# POWER_STAGE.net
KiCad netlist of a schematic drawn in Altium Designer
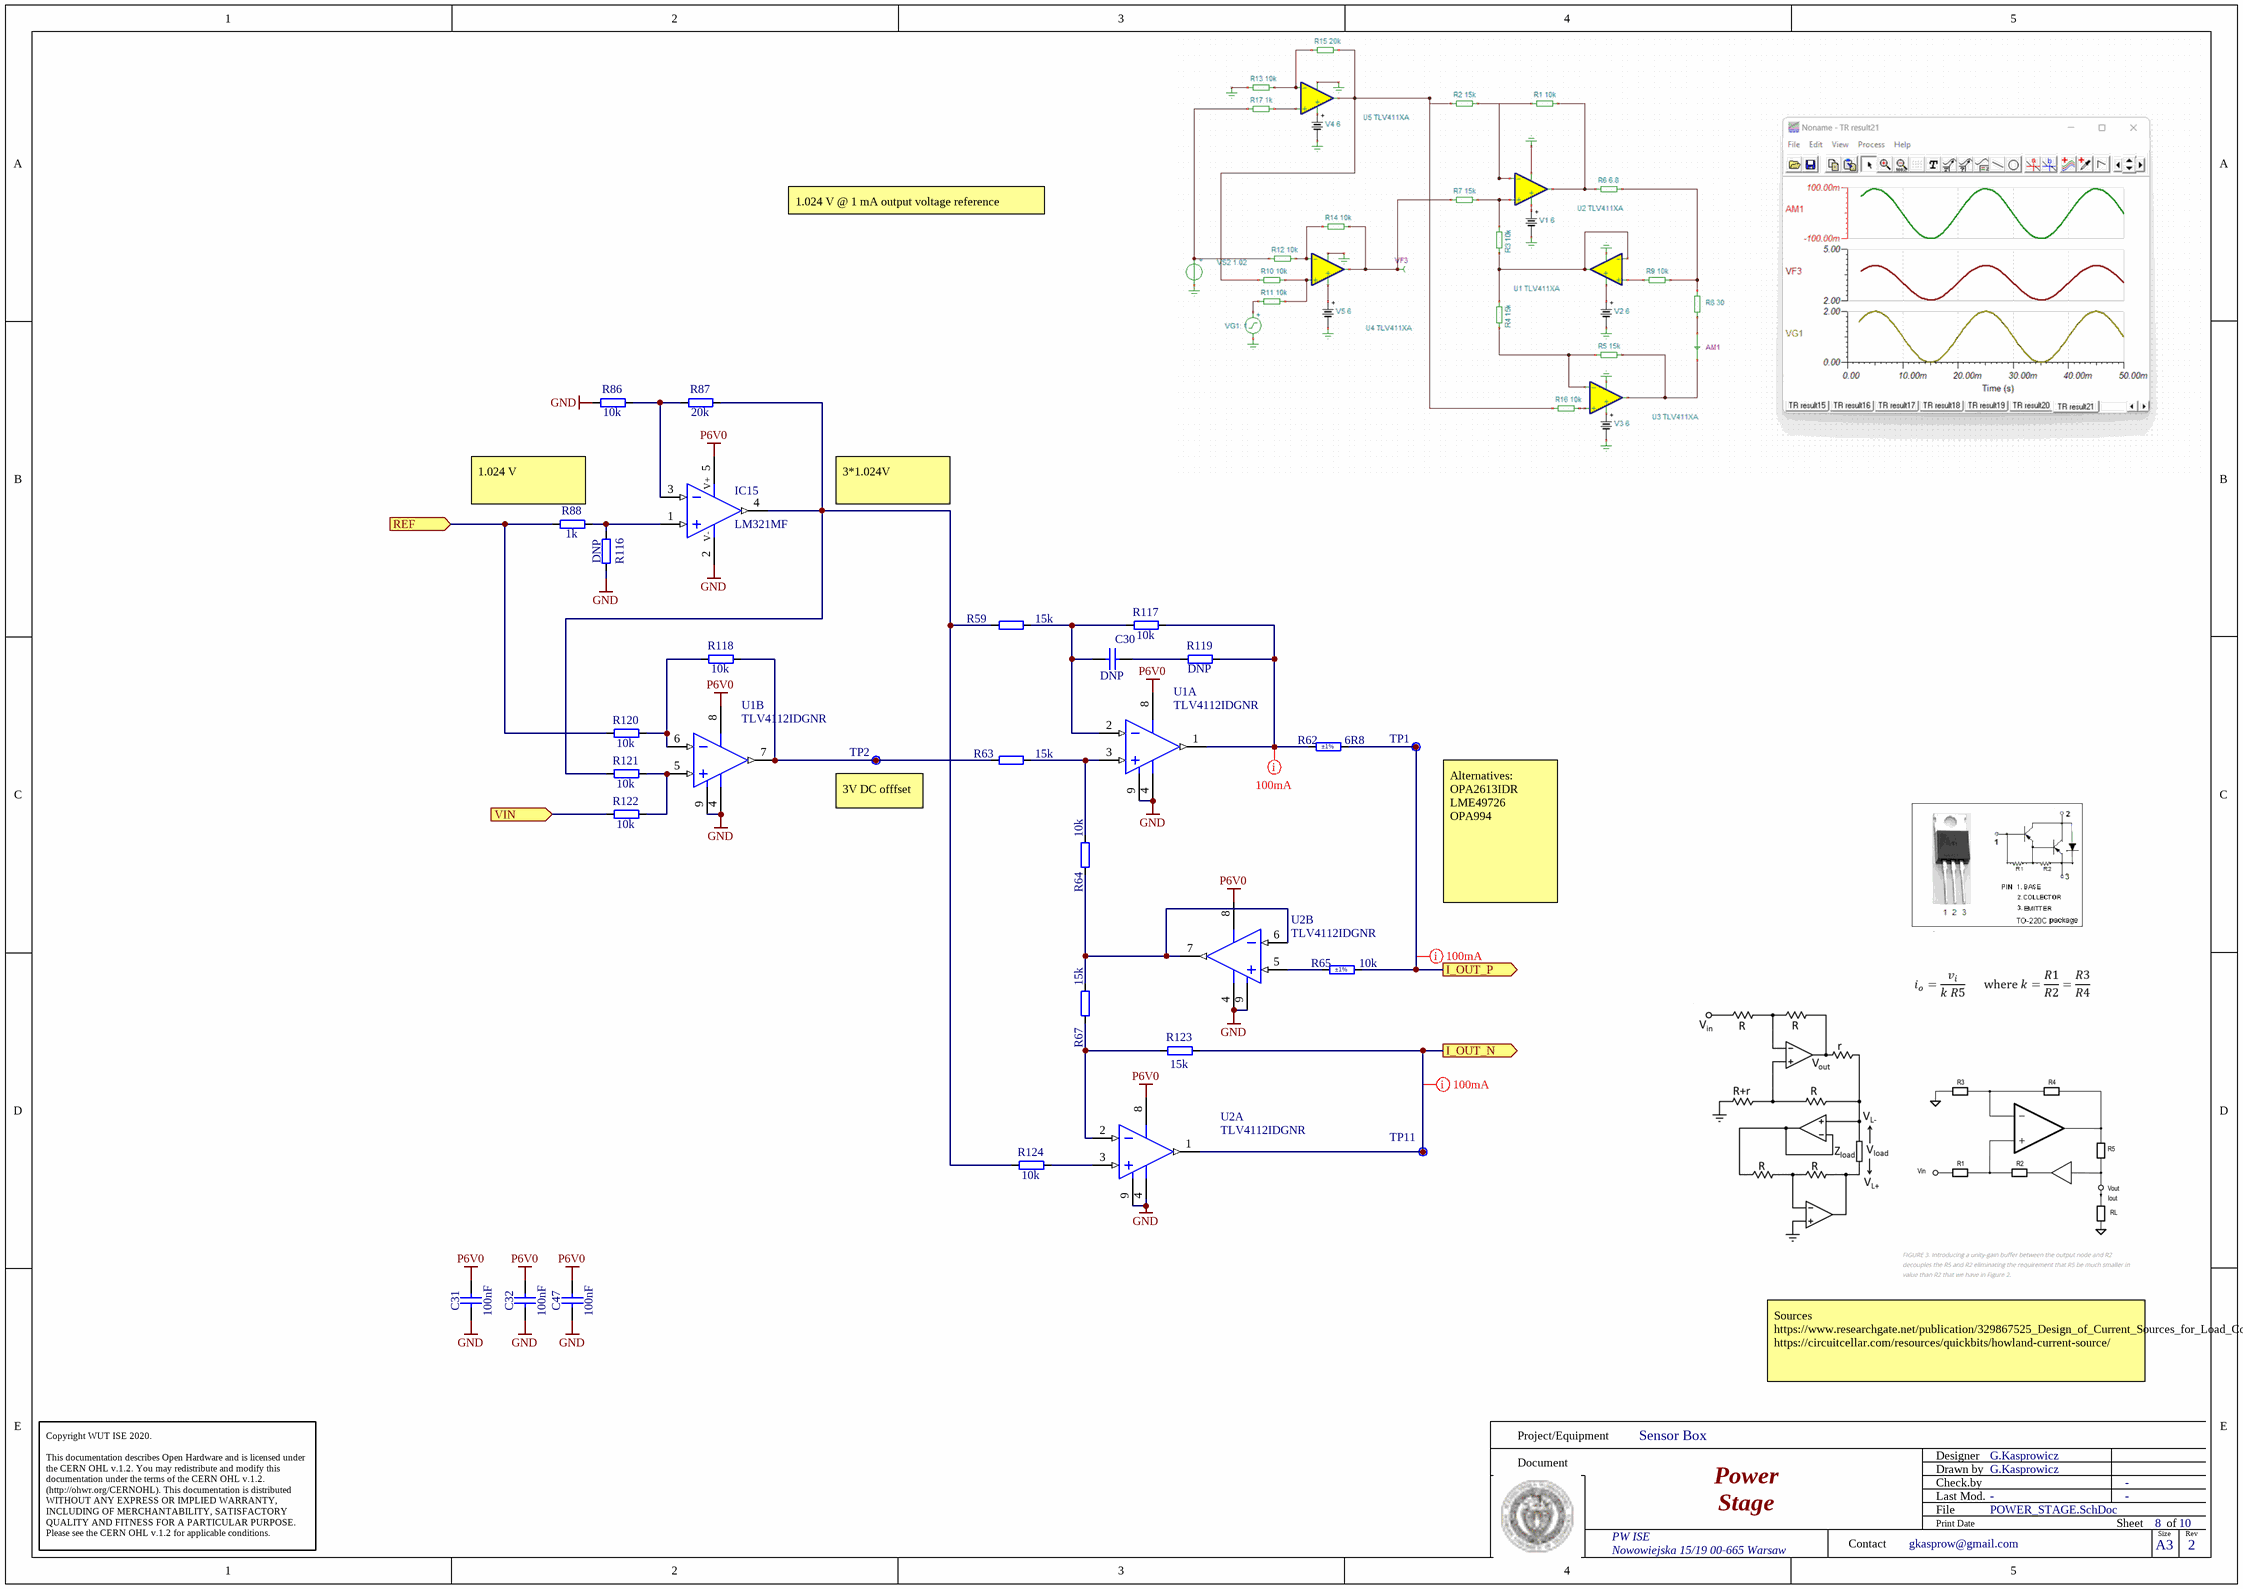
[diagram p0: POWER_STAGE.SchDoc]

(export (version "E")
  (design (tool "Eeschema 10.0.6"))
  (components
    (comp (ref "C30")
      (value "DNP")
      (footprint "CAPC1005X55N")
      (description "Non-polarised capacitor")
      (fields
        (field (name "PART NUMBER") "CC0402_100NF_16V_10%_X5R")
        (field (name "VOLTAGE") "16V")
        (field (name "AUTHOR") "CERN DEM JLC")
      )
      (libsource (lib "Capacitors") (part "Capacitor - non polarized"))
    )
    (comp (ref "C31")
      (value "100nF")
      (footprint "CAPC1005X55N")
      (description "Non-polarised capacitor")
      (fields
        (field (name "PART NUMBER") "CC0402_100NF_16V_10%_X5R")
        (field (name "VOLTAGE") "16V")
        (field (name "AUTHOR") "CERN DEM JLC")
      )
      (libsource (lib "Capacitors") (part "Capacitor - non polarized"))
    )
    (comp (ref "C32")
      (value "100nF")
      (footprint "CAPC1005X55N")
      (description "Non-polarised capacitor")
      (fields
        (field (name "PART NUMBER") "CC0402_100NF_16V_10%_X5R")
        (field (name "VOLTAGE") "16V")
        (field (name "AUTHOR") "CERN DEM JLC")
      )
      (libsource (lib "Capacitors") (part "Capacitor - non polarized"))
    )
    (comp (ref "C47")
      (value "100nF")
      (footprint "CAPC1005X55N")
      (description "Non-polarised capacitor")
      (fields
        (field (name "PART NUMBER") "CC0402_100NF_16V_10%_X5R")
        (field (name "VOLTAGE") "16V")
        (field (name "AUTHOR") "CERN DEM JLC")
      )
      (libsource (lib "Capacitors") (part "Capacitor - non polarized"))
    )
    (comp (ref "IC15")
      (value "LM321MF")
      (footprint "SOT95P280X145-5N")
      (description "Low Power Single Operational Amplifier")
      (fields
        (field (name "PART NUMBER") "LM321MF/NOPB")
        (field (name "MANUFACTURER") "TEXAS INSTRUMENTS")
        (field (name "AUTHOR") "CERN DEM BC")
      )
      (libsource (lib "ICs And Semiconductors") (part "LM321"))
    )
    (comp (ref "R59")
      (value "15k")
      (footprint "RESC1005X40N")
      (description "Resistor - 1%")
      (fields
        (field (name "PART NUMBER") "R0402_15K_1%_0.0625W_100PPM")
        (field (name "POWER") "0.0625W")
        (field (name "AUTHOR") "CERN DEM JMW")
      )
      (libsource (lib "Resistors") (part "Resistor - 1%"))
    )
    (comp (ref "R62")
      (value "6R8")
      (footprint "RESC6331X70N")
      (description "Resistor - 1%")
      (fields
        (field (name "TOLERANCE") "±1%")
        (field (name "PART NUMBER") "R2512_6R8_1%_1W_200PPM")
        (field (name "POWER") "1W")
        (field (name "AUTHOR") "CERN DEM JLC")
      )
      (libsource (lib "Resistors") (part "Resistor - 1%"))
    )
    (comp (ref "R63")
      (value "15k")
      (footprint "RESC1005X40N")
      (description "Resistor - 1%")
      (fields
        (field (name "PART NUMBER") "R0402_15K_1%_0.0625W_100PPM")
        (field (name "POWER") "0.0625W")
        (field (name "AUTHOR") "CERN DEM JMW")
      )
      (libsource (lib "Resistors") (part "Resistor - 1%"))
    )
    (comp (ref "R64")
      (value "10k")
      (footprint "RESC1005X40N")
      (description "Resistor - 1%")
      (fields
        (field (name "PART NUMBER") "R0402_10K_1%_0.0625W_100PPM")
        (field (name "POWER") "0.0625W")
        (field (name "AUTHOR") "CERN DEM JLC")
      )
      (libsource (lib "Resistors") (part "Resistor - 1%"))
    )
    (comp (ref "R65")
      (value "10k")
      (footprint "RESC1005X40N")
      (description "Resistor - 1%")
      (fields
        (field (name "PART NUMBER") "R0402_10K_1%_0.0625W_100PPM")
        (field (name "MANUFACTURER") "GENERIC")
        (field (name "TOLERANCE") "±1%")
        (field (name "AUTHOR") "CERN DEM JLC")
      )
      (libsource (lib "Resistors") (part "Resistor - 1%"))
    )
    (comp (ref "R67")
      (value "15k")
      (footprint "RESC1005X40N")
      (description "Resistor - 1%")
      (fields
        (field (name "PART NUMBER") "R0402_15K_1%_0.0625W_100PPM")
        (field (name "POWER") "0.0625W")
        (field (name "AUTHOR") "CERN DEM JMW")
      )
      (libsource (lib "Resistors") (part "Resistor - 1%"))
    )
    (comp (ref "R86")
      (value "10k")
      (footprint "RESC1005X40N")
      (description "Resistor - 1%")
      (fields
        (field (name "PART NUMBER") "R0402_10K_1%_0.0625W_100PPM")
        (field (name "POWER") "0.0625W")
        (field (name "AUTHOR") "CERN DEM JLC")
      )
      (libsource (lib "Resistors") (part "Resistor - 1%"))
    )
    (comp (ref "R87")
      (value "20k")
      (footprint "RESC1005X40N")
      (description "Resistor - 1%")
      (fields
        (field (name "PART NUMBER") "R0402_10K_1%_0.0625W_100PPM")
        (field (name "POWER") "0.0625W")
        (field (name "AUTHOR") "CERN DEM JLC")
      )
      (libsource (lib "Resistors") (part "Resistor - 1%"))
    )
    (comp (ref "R88")
      (value "1k")
      (footprint "RESC1005X40N")
      (description "Resistor - 1%")
      (fields
        (field (name "PART NUMBER") "R0402_10K_1%_0.0625W_100PPM")
        (field (name "POWER") "0.0625W")
        (field (name "AUTHOR") "CERN DEM JLC")
      )
      (libsource (lib "Resistors") (part "Resistor - 1%"))
    )
    (comp (ref "R116")
      (value "DNP")
      (footprint "RESC1005X40N")
      (description "Resistor - 1%")
      (fields
        (field (name "PART NUMBER") "R0402_10K_1%_0.0625W_100PPM")
        (field (name "POWER") "0.0625W")
        (field (name "AUTHOR") "CERN DEM JLC")
      )
      (libsource (lib "Resistors") (part "Resistor - 1%"))
    )
    (comp (ref "R117")
      (value "10k")
      (footprint "RESC1005X40N")
      (description "Resistor - 1%")
      (fields
        (field (name "PART NUMBER") "R0402_10K_1%_0.0625W_100PPM")
        (field (name "POWER") "0.0625W")
        (field (name "AUTHOR") "CERN DEM JLC")
      )
      (libsource (lib "Resistors") (part "Resistor - 1%"))
    )
    (comp (ref "R118")
      (value "10k")
      (footprint "RESC1005X40N")
      (description "Resistor - 1%")
      (fields
        (field (name "PART NUMBER") "R0402_10K_1%_0.0625W_100PPM")
        (field (name "POWER") "0.0625W")
        (field (name "AUTHOR") "CERN DEM JLC")
      )
      (libsource (lib "Resistors") (part "Resistor - 1%"))
    )
    (comp (ref "R119")
      (value "DNP")
      (footprint "RESC1005X40N")
      (description "Resistor - 1%")
      (fields
        (field (name "PART NUMBER") "R0402_10K_1%_0.0625W_100PPM")
        (field (name "POWER") "0.0625W")
        (field (name "AUTHOR") "CERN DEM JLC")
      )
      (libsource (lib "Resistors") (part "Resistor - 1%"))
    )
    (comp (ref "R120")
      (value "10k")
      (footprint "RESC1005X40N")
      (description "Resistor - 1%")
      (fields
        (field (name "PART NUMBER") "R0402_10K_1%_0.0625W_100PPM")
        (field (name "POWER") "0.0625W")
        (field (name "AUTHOR") "CERN DEM JLC")
      )
      (libsource (lib "Resistors") (part "Resistor - 1%"))
    )
    (comp (ref "R121")
      (value "10k")
      (footprint "RESC1005X40N")
      (description "Resistor - 1%")
      (fields
        (field (name "PART NUMBER") "R0402_10K_1%_0.0625W_100PPM")
        (field (name "POWER") "0.0625W")
        (field (name "AUTHOR") "CERN DEM JLC")
      )
      (libsource (lib "Resistors") (part "Resistor - 1%"))
    )
    (comp (ref "R122")
      (value "10k")
      (footprint "RESC1005X40N")
      (description "Resistor - 1%")
      (fields
        (field (name "PART NUMBER") "R0402_10K_1%_0.0625W_100PPM")
        (field (name "POWER") "0.0625W")
        (field (name "AUTHOR") "CERN DEM JLC")
      )
      (libsource (lib "Resistors") (part "Resistor - 1%"))
    )
    (comp (ref "R123")
      (value "15k")
      (footprint "RESC1005X40N")
      (description "Resistor - 1%")
      (fields
        (field (name "PART NUMBER") "R0402_15K_1%_0.0625W_100PPM")
        (field (name "POWER") "0.0625W")
        (field (name "AUTHOR") "CERN DEM JMW")
      )
      (libsource (lib "Resistors") (part "Resistor - 1%"))
    )
    (comp (ref "R124")
      (value "10k")
      (footprint "RESC1005X40N")
      (description "Resistor - 1%")
      (fields
        (field (name "PART NUMBER") "R0402_10K_1%_0.0625W_100PPM")
        (field (name "POWER") "0.0625W")
        (field (name "AUTHOR") "CERN DEM JLC")
      )
      (libsource (lib "Resistors") (part "Resistor - 1%"))
    )
    (comp (ref "TP1")
      (value "Plated Hole")
      (footprint "c130h60")
      (description "Single Terminal Socket")
      (fields (field (name "PART NUMBER") "PLATED_HOLE0.6_PAD1.3") (field (name "AUTHOR") "CERN DEM MR"))
      (libsource (lib "Eletro-mechanical") (part "Single Terminal Socket"))
    )
    (comp (ref "TP2")
      (value "Plated Hole")
      (footprint "c130h60")
      (description "Single Terminal Socket")
      (fields (field (name "PART NUMBER") "PLATED_HOLE0.6_PAD1.3") (field (name "AUTHOR") "CERN DEM MR"))
      (libsource (lib "Eletro-mechanical") (part "Single Terminal Socket"))
    )
    (comp (ref "TP11")
      (value "Plated Hole")
      (footprint "c130h60")
      (description "Single Terminal Socket")
      (fields (field (name "PART NUMBER") "PLATED_HOLE0.6_PAD1.3") (field (name "AUTHOR") "CERN DEM MR"))
      (libsource (lib "Eletro-mechanical") (part "Single Terminal Socket"))
    )
    (comp (ref "U1")
      (value "TLV4112IDGNR")
      (footprint "DGN0008D_N")
      (fields (field (name "MANUFACTURER") "Texas Instruments"))
      (libsource (lib "Altium Content Vault") (part "TI-TLV4112DGN8-1760X1425TP"))
    )
    (comp (ref "U2")
      (value "TLV4112IDGNR")
      (footprint "DGN0008D_N")
      (fields (field (name "MANUFACTURER") "Texas Instruments"))
      (libsource (lib "Altium Content Vault") (part "TI-TLV4112DGN8-1760X1425TP"))
    )
  )
  (nets
    (net (code "1") (name "/I_OUT_N") (class "Default")
      (node (ref "R123") (pin "2") (pinfunction "2_2") (pintype "passive"))
      (node (ref "TP11") (pin "1") (pinfunction "1_1") (pintype "bidirectional"))
      (node (ref "U2") (pin "1") (pinfunction "OUT1_1") (pintype "output"))
    )
    (net (code "2") (name "/I_OUT_P") (class "Default")
      (node (ref "R62") (pin "2") (pinfunction "2_2") (pintype "passive"))
      (node (ref "R65") (pin "2") (pinfunction "2_2") (pintype "passive"))
      (node (ref "TP1") (pin "1") (pinfunction "1_1") (pintype "bidirectional"))
    )
    (net (code "3") (name "/REF") (class "Default")
      (node (ref "R120") (pin "1") (pinfunction "1_1") (pintype "passive"))
      (node (ref "R88") (pin "1") (pinfunction "1_1") (pintype "passive"))
    )
    (net (code "4") (name "/VIN") (class "Default")
      (node (ref "R122") (pin "1") (pinfunction "1_1") (pintype "passive"))
    )
    (net (code "5") (name "GND") (class "Default")
      (node (ref "C31") (pin "1") (pinfunction "1_1") (pintype "passive"))
      (node (ref "C32") (pin "1") (pinfunction "1_1") (pintype "passive"))
      (node (ref "C47") (pin "1") (pinfunction "1_1") (pintype "passive"))
      (node (ref "IC15") (pin "2") (pinfunction "V-_2") (pintype "power_in"))
      (node (ref "R116") (pin "2") (pinfunction "2_2") (pintype "passive"))
      (node (ref "R86") (pin "1") (pinfunction "1_1") (pintype "passive"))
      (node (ref "U1") (pin "4") (pinfunction "GND_4") (pintype "power_in"))
      (node (ref "U1") (pin "9") (pinfunction "EP_9") (pintype "power_in"))
      (node (ref "U2") (pin "4") (pinfunction "GND_4") (pintype "power_in"))
      (node (ref "U2") (pin "9") (pinfunction "EP_9") (pintype "power_in"))
    )
    (net (code "6") (name "Net-(C30-Pad2)") (class "Default")
      (node (ref "C30") (pin "2") (pinfunction "2_2") (pintype "passive"))
      (node (ref "R119") (pin "1") (pinfunction "1_1") (pintype "passive"))
    )
    (net (code "7") (name "Net-(IC15-IN+)") (class "Default")
      (node (ref "IC15") (pin "1") (pinfunction "IN+_1") (pintype "input"))
      (node (ref "R116") (pin "1") (pinfunction "1_1") (pintype "passive"))
      (node (ref "R88") (pin "2") (pinfunction "2_2") (pintype "passive"))
    )
    (net (code "8") (name "Net-(IC15-IN-)") (class "Default")
      (node (ref "IC15") (pin "3") (pinfunction "IN-_3") (pintype "input"))
      (node (ref "R86") (pin "2") (pinfunction "2_2") (pintype "passive"))
      (node (ref "R87") (pin "1") (pinfunction "1_1") (pintype "passive"))
    )
    (net (code "9") (name "Net-(IC15-OUT)") (class "Default")
      (node (ref "IC15") (pin "4") (pinfunction "OUT_4") (pintype "output"))
      (node (ref "R121") (pin "1") (pinfunction "1_1") (pintype "passive"))
      (node (ref "R124") (pin "1") (pinfunction "1_1") (pintype "passive"))
      (node (ref "R59") (pin "1") (pinfunction "1_1") (pintype "passive"))
      (node (ref "R87") (pin "2") (pinfunction "2_2") (pintype "passive"))
    )
    (net (code "10") (name "Net-(U1A-IN1+)") (class "Default")
      (node (ref "R63") (pin "2") (pinfunction "2_2") (pintype "passive"))
      (node (ref "R64") (pin "1") (pinfunction "1_1") (pintype "passive"))
      (node (ref "U1") (pin "3") (pinfunction "IN1+_3") (pintype "input"))
    )
    (net (code "11") (name "Net-(U1A-IN1-)") (class "Default")
      (node (ref "C30") (pin "1") (pinfunction "1_1") (pintype "passive"))
      (node (ref "R117") (pin "1") (pinfunction "1_1") (pintype "passive"))
      (node (ref "R59") (pin "2") (pinfunction "2_2") (pintype "passive"))
      (node (ref "U1") (pin "2") (pinfunction "IN1-_2") (pintype "input"))
    )
    (net (code "12") (name "Net-(U1A-OUT1)") (class "Default")
      (node (ref "R117") (pin "2") (pinfunction "2_2") (pintype "passive"))
      (node (ref "R119") (pin "2") (pinfunction "2_2") (pintype "passive"))
      (node (ref "R62") (pin "1") (pinfunction "1_1") (pintype "passive"))
      (node (ref "U1") (pin "1") (pinfunction "OUT1_1") (pintype "output"))
    )
    (net (code "13") (name "Net-(U1B-IN2+)") (class "Default")
      (node (ref "R121") (pin "2") (pinfunction "2_2") (pintype "passive"))
      (node (ref "R122") (pin "2") (pinfunction "2_2") (pintype "passive"))
      (node (ref "U1") (pin "5") (pinfunction "IN2+_5") (pintype "input"))
    )
    (net (code "14") (name "Net-(U1B-IN2-)") (class "Default")
      (node (ref "R118") (pin "1") (pinfunction "1_1") (pintype "passive"))
      (node (ref "R120") (pin "2") (pinfunction "2_2") (pintype "passive"))
      (node (ref "U1") (pin "6") (pinfunction "IN2-_6") (pintype "input"))
    )
    (net (code "15") (name "Net-(U1B-OUT2)") (class "Default")
      (node (ref "R118") (pin "2") (pinfunction "2_2") (pintype "passive"))
      (node (ref "R63") (pin "1") (pinfunction "1_1") (pintype "passive"))
      (node (ref "TP2") (pin "1") (pinfunction "1_1") (pintype "bidirectional"))
      (node (ref "U1") (pin "7") (pinfunction "OUT2_7") (pintype "output"))
    )
    (net (code "16") (name "Net-(U2A-IN1+)") (class "Default")
      (node (ref "R124") (pin "2") (pinfunction "2_2") (pintype "passive"))
      (node (ref "U2") (pin "3") (pinfunction "IN1+_3") (pintype "input"))
    )
    (net (code "17") (name "Net-(U2A-IN1-)") (class "Default")
      (node (ref "R123") (pin "1") (pinfunction "1_1") (pintype "passive"))
      (node (ref "R67") (pin "1") (pinfunction "1_1") (pintype "passive"))
      (node (ref "U2") (pin "2") (pinfunction "IN1-_2") (pintype "input"))
    )
    (net (code "18") (name "Net-(U2B-IN2+)") (class "Default")
      (node (ref "R65") (pin "1") (pinfunction "1_1") (pintype "passive"))
      (node (ref "U2") (pin "5") (pinfunction "IN2+_5") (pintype "input"))
    )
    (net (code "19") (name "Net-(U2B-IN2-)") (class "Default")
      (node (ref "R64") (pin "2") (pinfunction "2_2") (pintype "passive"))
      (node (ref "R67") (pin "2") (pinfunction "2_2") (pintype "passive"))
      (node (ref "U2") (pin "6") (pinfunction "IN2-_6") (pintype "input"))
      (node (ref "U2") (pin "7") (pinfunction "OUT2_7") (pintype "output"))
    )
    (net (code "20") (name "P6V0") (class "Default")
      (node (ref "C31") (pin "2") (pinfunction "2_2") (pintype "passive"))
      (node (ref "C32") (pin "2") (pinfunction "2_2") (pintype "passive"))
      (node (ref "C47") (pin "2") (pinfunction "2_2") (pintype "passive"))
      (node (ref "IC15") (pin "5") (pinfunction "V+_5") (pintype "power_in"))
      (node (ref "U1") (pin "8") (pinfunction "VDD+_8") (pintype "power_in"))
      (node (ref "U2") (pin "8") (pinfunction "VDD+_8") (pintype "power_in"))
    )
  )
)
